# room8266.net
KiCad netlist of a schematic drawn in EAGLE
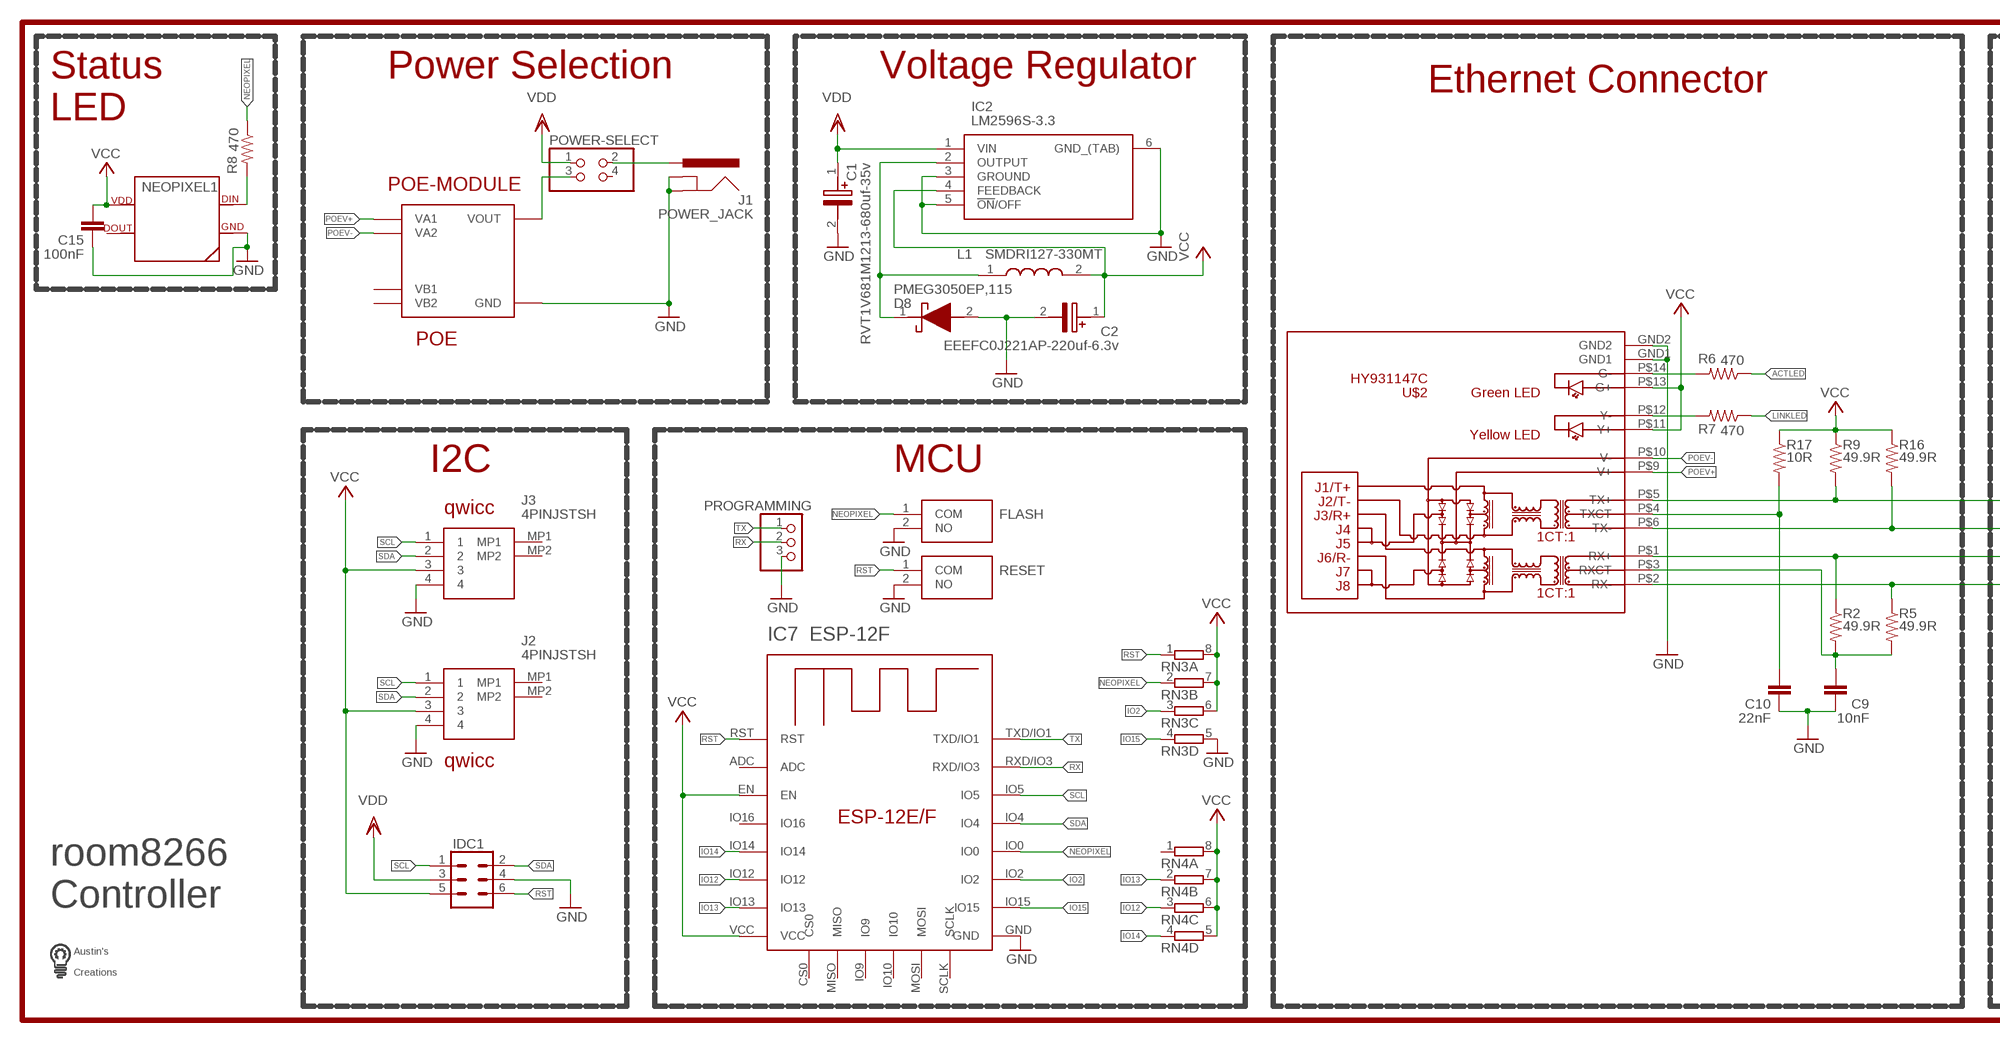
[diagram p0: schematic, sheet 1, part 1 of 2]
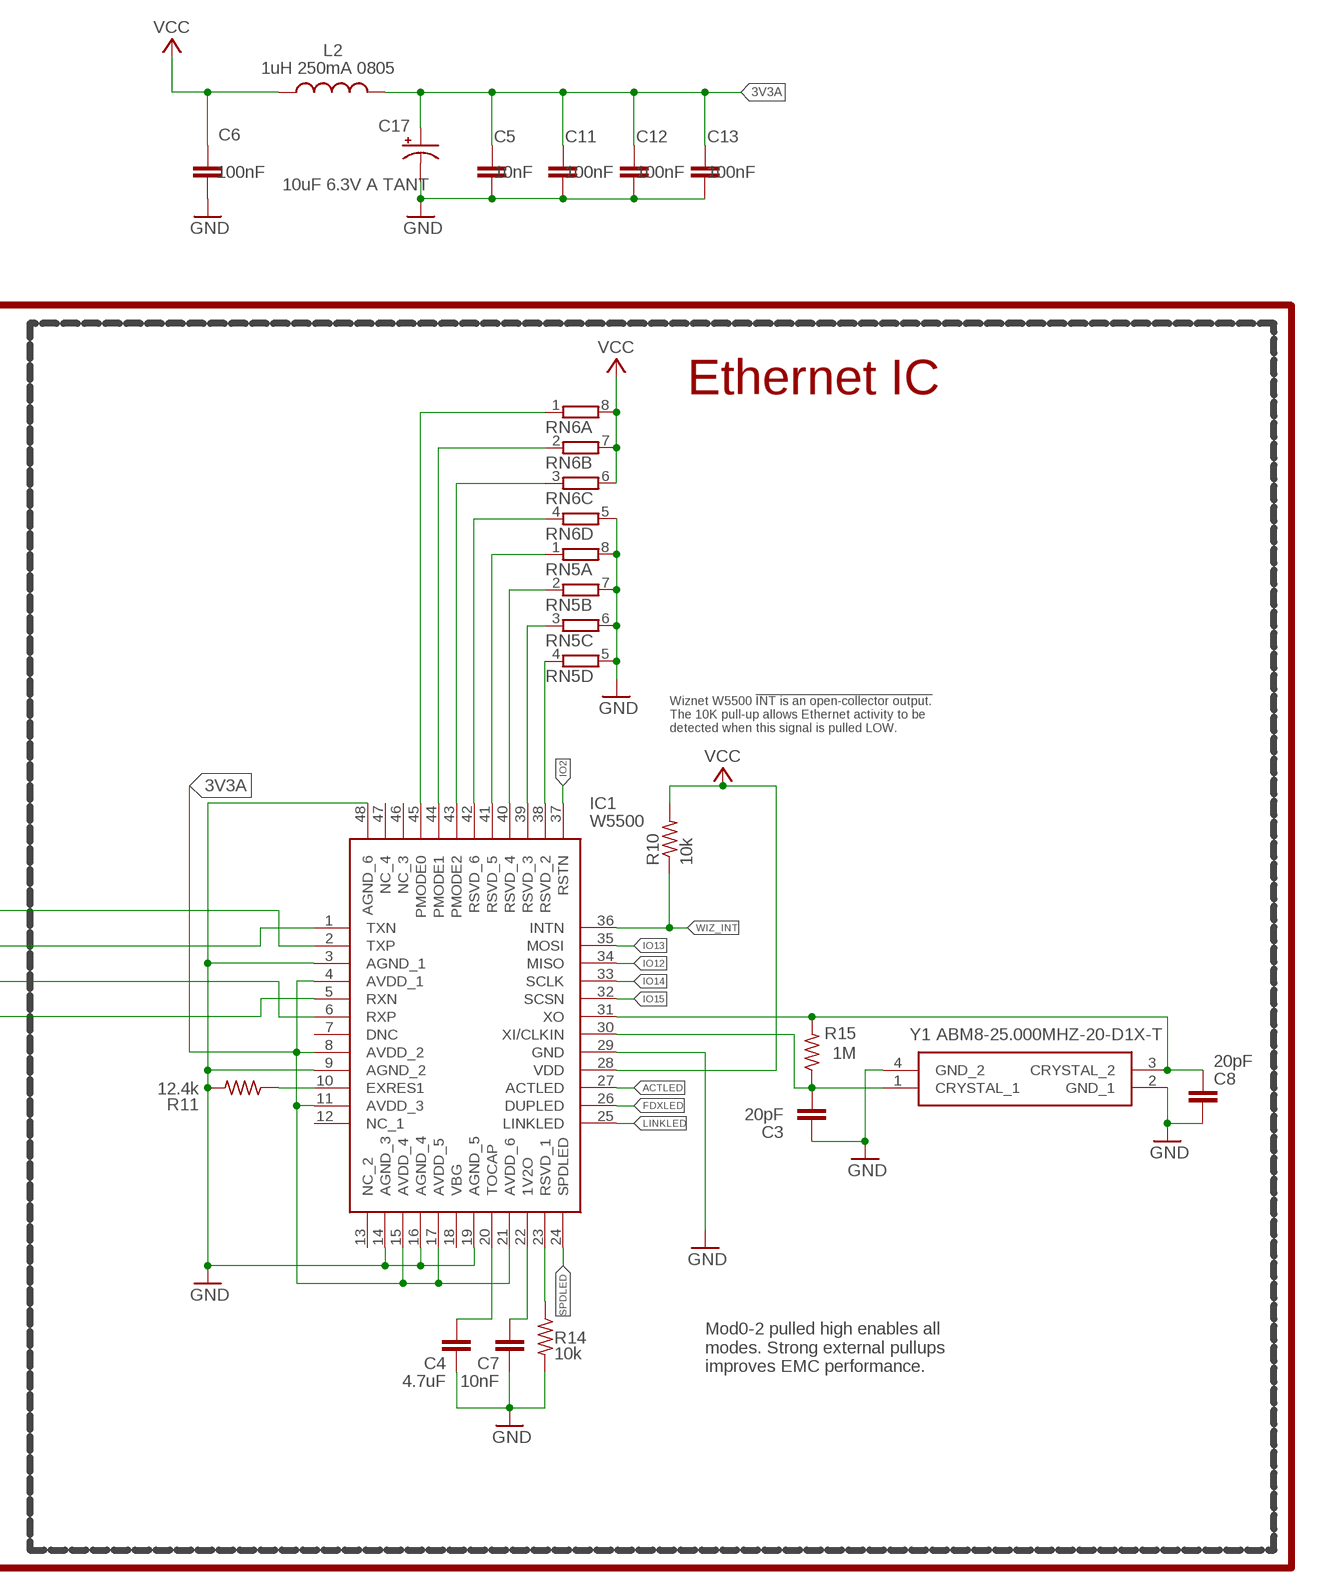
[diagram p1: schematic, sheet 1, part 2 of 2]

(export (version "E")
  (design (tool "Eeschema 10.0.6"))
  (components
    (comp (ref "C1")
      (value "RVT1V681M1213-680uf-35v")
      (footprint "eagle-import:CAPAE1350X1400N")
      (fields
        (field (name "MANUFACTURER_PART_NUMBER") "EEE-HD1V681AQ")
        (field (name "MOUSER_PART_NUMBER") "667-EEE-HD1V681AQ")
      )
      (libsource (lib "eagle-import") (part "EEE-HD1V681AQ"))
    )
    (comp (ref "C2")
      (value "EEEFC0J221AP-220uf-6.3v")
      (footprint "eagle-import:CAPAE830X650N")
      (fields (field (name "MANUFACTURER_PART_NUMBER") "EEEFC0J221AP"))
      (libsource (lib "eagle-import") (part "EEEFC0J221AP"))
    )
    (comp (ref "C3")
      (value "20pF")
      (footprint "eagle-import:C0603")
      (libsource (lib "eagle-import") (part "resistor_348_C-EUC0603"))
    )
    (comp (ref "C4")
      (value "4.7uF")
      (footprint "eagle-import:C0603")
      (libsource (lib "eagle-import") (part "resistor_348_C-EUC0603"))
    )
    (comp (ref "C5")
      (value "10nF")
      (footprint "eagle-import:C0603")
      (libsource (lib "eagle-import") (part "C-EUC0603"))
    )
    (comp (ref "C6")
      (value "100nF")
      (footprint "eagle-import:C0603")
      (libsource (lib "eagle-import") (part "C-EUC0603"))
    )
    (comp (ref "C7")
      (value "10nF")
      (footprint "eagle-import:C0603")
      (libsource (lib "eagle-import") (part "resistor_348_C-EUC0603"))
    )
    (comp (ref "C8")
      (value "20pF")
      (footprint "eagle-import:C0603")
      (libsource (lib "eagle-import") (part "resistor_348_C-EUC0603"))
    )
    (comp (ref "C9")
      (value "10nF")
      (footprint "eagle-import:C0603")
      (libsource (lib "eagle-import") (part "resistor_348_C-EUC0603"))
    )
    (comp (ref "C10")
      (value "22nF")
      (footprint "eagle-import:C0603")
      (libsource (lib "eagle-import") (part "resistor_348_C-EUC0603"))
    )
    (comp (ref "C11")
      (value "100nF")
      (footprint "eagle-import:C0603")
      (libsource (lib "eagle-import") (part "C-EUC0603"))
    )
    (comp (ref "C12")
      (value "100nF")
      (footprint "eagle-import:C0603")
      (libsource (lib "eagle-import") (part "C-EUC0603"))
    )
    (comp (ref "C13")
      (value "100nF")
      (footprint "eagle-import:C0603")
      (libsource (lib "eagle-import") (part "C-EUC0603"))
    )
    (comp (ref "C15")
      (value "100nF")
      (footprint "eagle-import:C0603")
      (libsource (lib "eagle-import") (part "resistor_348_C-EUC0603"))
    )
    (comp (ref "C17")
      (value "10uF 6.3V A TANT")
      (footprint "eagle-import:A_3216-18W")
      (libsource (lib "eagle-import") (part "CPOL-USA/3216-18W"))
    )
    (comp (ref "D8")
      (value "PMEG3050EP,115")
      (footprint "eagle-import:PMEG3050EP115")
      (fields (field (name "MOUSER_PART_NUMBER") "771-PMEG3050EP115"))
      (libsource (lib "eagle-import") (part "PMEG3050EP,115"))
    )
    (comp (ref "FLASH")
      (value "PTS636_SM25F_SMTR_LFS")
      (footprint "eagle-import:PTS636SM25FSMTRLFS")
      (fields
        (field (name "ARROW_PART_NUMBER") "PTS636 SM25F SMTR LFS")
        (field (name "MOUSER_PART_NUMBER") "611-PTS636SM25FSMTRL")
      )
      (libsource (lib "eagle-import") (part "PTS636_SM25F_SMTR_LFS"))
    )
    (comp (ref "IC1")
      (value "W5500")
      (footprint "eagle-import:QFP50P900X900X160-48N")
      (fields (field (name "MOUSER_PART_NUMBER") "950-W5500"))
      (libsource (lib "eagle-import") (part "W5500"))
    )
    (comp (ref "IC2")
      (value "LM2596S-3.3")
      (footprint "eagle-import:TO170P1435X465-6N")
      (fields
        (field (name "MANUFACTURER_PART_NUMBER") "LM2596S-3.3/NOPB")
        (field (name "MOUSER_PART_NUMBER") "926-LM2596S-3.3/NOPB")
      )
      (libsource (lib "eagle-import") (part "LM2596S-3.3_NOPB"))
    )
    (comp (ref "IC7")
      (value "ESP-12F")
      (footprint "eagle-import:ESP-12E")
      (libsource (lib "eagle-import") (part "ESP-12E/F"))
    )
    (comp (ref "IDC1")
      (value "CONN_03X2SHROUD")
      (footprint "eagle-import:2X3-SHROUDED")
      (libsource (lib "eagle-import") (part "CONN_03X2SHROUD"))
    )
    (comp (ref "J1")
      (value "POWER_JACK")
      (footprint "eagle-import:POWER_JACK_PTH")
      (libsource (lib "eagle-import") (part "POWER_JACK"))
    )
    (comp (ref "J2")
      (value "4PINJSTSH")
      (footprint "eagle-import:665104131822")
      (fields
        (field (name "MANUFACTURER_PART_NUMBER") "665104131822")
        (field (name "MOUSER_PART_NUMBER") "710-665104131822")
      )
      (libsource (lib "eagle-import") (part "4PINJSTSH"))
    )
    (comp (ref "J3")
      (value "4PINJSTSH")
      (footprint "eagle-import:665104131822")
      (fields
        (field (name "MANUFACTURER_PART_NUMBER") "665104131822")
        (field (name "MOUSER_PART_NUMBER") "710-665104131822")
      )
      (libsource (lib "eagle-import") (part "4PINJSTSH"))
    )
    (comp (ref "L1")
      (value "SMDRI127-330MT")
      (footprint "eagle-import:INDPM120120X800N")
      (fields
        (field (name "MANUFACTURER_PART_NUMBER") "CDRH127/LDNP-330MC")
        (field (name "MOUSER_PART_NUMBER") "851-CDRH127LDNP330MC")
      )
      (libsource (lib "eagle-import") (part "CDRH127_LDNP-330MC"))
    )
    (comp (ref "L2")
      (value "1uH 250mA 0805")
      (footprint "eagle-import:L2012C")
      (libsource (lib "eagle-import") (part "L-USL2012C"))
    )
    (comp (ref "NEOPIXEL1")
      (value "SK6812NEOPIXEL5050")
      (footprint "eagle-import:SK6812")
      (libsource (lib "eagle-import") (part "SK68125050NEOPIXEL"))
    )
    (comp (ref "POE-MODULE")
      (value "POE")
      (footprint "eagle-import:DP1435")
      (libsource (lib "eagle-import") (part "POE"))
    )
    (comp (ref "POWER-SELECT")
      (value "PINHD-2X2")
      (footprint "eagle-import:2X02")
      (libsource (lib "eagle-import") (part "PINHD-2X2"))
    )
    (comp (ref "PROGRAMMING")
      (value "PINHD-1X3")
      (footprint "eagle-import:1X03")
      (libsource (lib "eagle-import") (part "PINHD-1X3"))
    )
    (comp (ref "R2")
      (value "49.9R")
      (footprint "eagle-import:R0603")
      (libsource (lib "eagle-import") (part "R-US_R0603"))
    )
    (comp (ref "R5")
      (value "49.9R")
      (footprint "eagle-import:R0603")
      (libsource (lib "eagle-import") (part "R-US_R0603"))
    )
    (comp (ref "R6")
      (value "470")
      (footprint "eagle-import:R0603")
      (libsource (lib "eagle-import") (part "R-US_R0603"))
    )
    (comp (ref "R7")
      (value "470")
      (footprint "eagle-import:R0603")
      (libsource (lib "eagle-import") (part "R-US_R0603"))
    )
    (comp (ref "R8")
      (value "470")
      (footprint "eagle-import:R0603")
      (libsource (lib "eagle-import") (part "R-US_R0603"))
    )
    (comp (ref "R9")
      (value "49.9R")
      (footprint "eagle-import:R0603")
      (libsource (lib "eagle-import") (part "R-US_R0603"))
    )
    (comp (ref "R10")
      (value "10k")
      (footprint "eagle-import:R0603")
      (libsource (lib "eagle-import") (part "R-US_R0603"))
    )
    (comp (ref "R11")
      (value "12.4k")
      (footprint "eagle-import:R0603")
      (libsource (lib "eagle-import") (part "R-US_R0603"))
    )
    (comp (ref "R14")
      (value "10k")
      (footprint "eagle-import:R0603")
      (libsource (lib "eagle-import") (part "R-US_R0603"))
    )
    (comp (ref "R15")
      (value "1M")
      (footprint "eagle-import:R0603")
      (libsource (lib "eagle-import") (part "R-US_R0603"))
    )
    (comp (ref "R16")
      (value "49.9R")
      (footprint "eagle-import:R0603")
      (libsource (lib "eagle-import") (part "R-US_R0603"))
    )
    (comp (ref "R17")
      (value "10R")
      (footprint "eagle-import:R0603")
      (libsource (lib "eagle-import") (part "R-US_R0603"))
    )
    (comp (ref "RESET")
      (value "PTS636_SM25F_SMTR_LFS")
      (footprint "eagle-import:PTS636SM25FSMTRLFS")
      (fields
        (field (name "ARROW_PART_NUMBER") "PTS636 SM25F SMTR LFS")
        (field (name "MOUSER_PART_NUMBER") "611-PTS636SM25FSMTRL")
      )
      (libsource (lib "eagle-import") (part "PTS636_SM25F_SMTR_LFS"))
    )
    (comp (ref "RN3")
      (value "4R-N0603-ARC")
      (footprint "eagle-import:0603-ARC")
      (libsource (lib "eagle-import") (part "4R-N0603-ARC"))
    )
    (comp (ref "RN4")
      (value "4R-N0603-ARC")
      (footprint "eagle-import:0603-ARC")
      (libsource (lib "eagle-import") (part "4R-N0603-ARC"))
    )
    (comp (ref "RN5")
      (value "4R-N0603-ARC")
      (footprint "eagle-import:0603-ARC")
      (libsource (lib "eagle-import") (part "4R-N0603-ARC"))
    )
    (comp (ref "RN6")
      (value "4R-N0603-ARC")
      (footprint "eagle-import:0603-ARC")
      (libsource (lib "eagle-import") (part "4R-N0603-ARC"))
    )
    (comp (ref "U$1")
      (value "LOGOMED")
      (footprint "eagle-import:LOGOMED")
      (libsource (lib "eagle-import") (part "LOGOMED"))
    )
    (comp (ref "U$2")
      (value "HY931147C")
      (footprint "eagle-import:HY931147C")
      (libsource (lib "eagle-import") (part "HY931147C"))
    )
    (comp (ref "Y1")
      (value "ABM8-25.000MHZ-20-D1X-T")
      (footprint "eagle-import:ABM825000MHZ10B1UT")
      (fields
        (field (name "MANUFACTURER_PART_NUMBER") "ABM8-25.000MHz-20-D1X-T")
        (field (name "MOUSER_PART_NUMBER") "815-M825000MHZ20D1XT")
      )
      (libsource (lib "eagle-import") (part "ABM8-25.000MHZ-20-D1X-T"))
    )
  )
  (nets
    (net (code "1") (name "3V3A") (class "Default")
      (node (ref "C11") (pin "1") (pinfunction "1_1") (pintype "passive"))
      (node (ref "C12") (pin "1") (pinfunction "1_1") (pintype "passive"))
      (node (ref "C13") (pin "1") (pinfunction "1_1") (pintype "passive"))
      (node (ref "C17") (pin "+") (pinfunction "+_+") (pintype "passive"))
      (node (ref "C5") (pin "1") (pinfunction "1_1") (pintype "passive"))
      (node (ref "IC1") (pin "11") (pinfunction "AVDD_3_11") (pintype "bidirectional"))
      (node (ref "IC1") (pin "15") (pinfunction "AVDD_4_15") (pintype "bidirectional"))
      (node (ref "IC1") (pin "17") (pinfunction "AVDD_5_17") (pintype "bidirectional"))
      (node (ref "IC1") (pin "21") (pinfunction "AVDD_6_21") (pintype "bidirectional"))
      (node (ref "IC1") (pin "4") (pinfunction "AVDD_1_4") (pintype "bidirectional"))
      (node (ref "IC1") (pin "8") (pinfunction "AVDD_2_8") (pintype "bidirectional"))
      (node (ref "L2") (pin "2") (pinfunction "2_2") (pintype "passive"))
    )
    (net (code "2") (name "ACTLED") (class "Default")
      (node (ref "IC1") (pin "27") (pinfunction "ACTLED_27") (pintype "bidirectional"))
      (node (ref "R6") (pin "1") (pinfunction "1_1") (pintype "passive"))
    )
    (net (code "3") (name "FDXLED") (class "Default")
      (node (ref "IC1") (pin "26") (pinfunction "DUPLED_26") (pintype "bidirectional"))
    )
    (net (code "4") (name "GND") (class "Default")
      (node (ref "C1") (pin "2") (pinfunction "-_2") (pintype "bidirectional"))
      (node (ref "C10") (pin "1") (pinfunction "1_1") (pintype "passive"))
      (node (ref "C11") (pin "2") (pinfunction "2_2") (pintype "passive"))
      (node (ref "C12") (pin "2") (pinfunction "2_2") (pintype "passive"))
      (node (ref "C13") (pin "2") (pinfunction "2_2") (pintype "passive"))
      (node (ref "C15") (pin "1") (pinfunction "1_1") (pintype "passive"))
      (node (ref "C17") (pin "-") (pinfunction "-_-") (pintype "passive"))
      (node (ref "C2") (pin "2") (pinfunction "-_2") (pintype "bidirectional"))
      (node (ref "C3") (pin "1") (pinfunction "1_1") (pintype "passive"))
      (node (ref "C4") (pin "1") (pinfunction "1_1") (pintype "passive"))
      (node (ref "C5") (pin "2") (pinfunction "2_2") (pintype "passive"))
      (node (ref "C6") (pin "2") (pinfunction "2_2") (pintype "passive"))
      (node (ref "C7") (pin "1") (pinfunction "1_1") (pintype "passive"))
      (node (ref "C8") (pin "1") (pinfunction "1_1") (pintype "passive"))
      (node (ref "C9") (pin "1") (pinfunction "1_1") (pintype "passive"))
      (node (ref "D8") (pin "2") (pinfunction "A_2") (pintype "bidirectional"))
      (node (ref "FLASH") (pin "2") (pinfunction "NO_2") (pintype "bidirectional"))
      (node (ref "IC1") (pin "14") (pinfunction "AGND_3_14") (pintype "bidirectional"))
      (node (ref "IC1") (pin "16") (pinfunction "AGND_4_16") (pintype "bidirectional"))
      (node (ref "IC1") (pin "19") (pinfunction "AGND_5_19") (pintype "bidirectional"))
      (node (ref "IC1") (pin "29") (pinfunction "GND_29") (pintype "bidirectional"))
      (node (ref "IC1") (pin "3") (pinfunction "AGND_1_3") (pintype "bidirectional"))
      (node (ref "IC1") (pin "48") (pinfunction "AGND_6_48") (pintype "bidirectional"))
      (node (ref "IC1") (pin "9") (pinfunction "AGND_2_9") (pintype "bidirectional"))
      (node (ref "IC2") (pin "3") (pinfunction "GROUND_3") (pintype "bidirectional"))
      (node (ref "IC2") (pin "5") (pinfunction "~{ON}/OFF_5") (pintype "bidirectional"))
      (node (ref "IC2") (pin "6") (pinfunction "GND_(TAB)_6") (pintype "power_in"))
      (node (ref "IC7") (pin "GND") (pinfunction "GND_GND") (pintype "power_in"))
      (node (ref "IDC1") (pin "4") (pinfunction "4_4") (pintype "bidirectional"))
      (node (ref "J1") (pin "GND") (pinfunction "GND_GND") (pintype "bidirectional"))
      (node (ref "J1") (pin "GNDBREAK") (pinfunction "GNDBREAK_GNDBREAK") (pintype "bidirectional"))
      (node (ref "J2") (pin "4") (pinfunction "4_4") (pintype "bidirectional"))
      (node (ref "J3") (pin "4") (pinfunction "4_4") (pintype "bidirectional"))
      (node (ref "NEOPIXEL1") (pin "3") (pinfunction "GND_3") (pintype "bidirectional"))
      (node (ref "POE-MODULE") (pin "GND") (pinfunction "GND_GND") (pintype "bidirectional"))
      (node (ref "PROGRAMMING") (pin "3") (pinfunction "3_3") (pintype "passive"))
      (node (ref "R11") (pin "2") (pinfunction "2_2") (pintype "passive"))
      (node (ref "R14") (pin "2") (pinfunction "2_2") (pintype "passive"))
      (node (ref "RESET") (pin "2") (pinfunction "NO_2") (pintype "bidirectional"))
      (node (ref "RN3") (pin "5") (pinfunction "2_5") (pintype "passive"))
      (node (ref "RN5") (pin "5") (pinfunction "2_5") (pintype "passive"))
      (node (ref "RN5") (pin "6") (pinfunction "2_6") (pintype "passive"))
      (node (ref "RN5") (pin "7") (pinfunction "2_7") (pintype "passive"))
      (node (ref "RN5") (pin "8") (pinfunction "2_8") (pintype "passive"))
      (node (ref "RN6") (pin "5") (pinfunction "2_5") (pintype "passive"))
      (node (ref "U$2") (pin "GND1") (pinfunction "GND1_GND1") (pintype "bidirectional"))
      (node (ref "U$2") (pin "GND2") (pinfunction "GND2_GND2") (pintype "bidirectional"))
      (node (ref "Y1") (pin "2") (pinfunction "GND_1_2") (pintype "bidirectional"))
      (node (ref "Y1") (pin "4") (pinfunction "GND_2_4") (pintype "bidirectional"))
    )
    (net (code "5") (name "IO2") (class "Default")
      (node (ref "IC1") (pin "37") (pinfunction "RSTN_37") (pintype "bidirectional"))
      (node (ref "IC7") (pin "IO2") (pinfunction "IO2_IO2") (pintype "bidirectional"))
      (node (ref "RN3") (pin "3") (pinfunction "1_3") (pintype "passive"))
    )
    (net (code "6") (name "IO12") (class "Default")
      (node (ref "IC1") (pin "34") (pinfunction "MISO_34") (pintype "bidirectional"))
      (node (ref "IC7") (pin "IO12") (pinfunction "IO12_IO12") (pintype "bidirectional"))
      (node (ref "RN4") (pin "3") (pinfunction "1_3") (pintype "passive"))
    )
    (net (code "7") (name "IO13") (class "Default")
      (node (ref "IC1") (pin "35") (pinfunction "MOSI_35") (pintype "bidirectional"))
      (node (ref "IC7") (pin "IO13") (pinfunction "IO13_IO13") (pintype "bidirectional"))
      (node (ref "RN4") (pin "2") (pinfunction "1_2") (pintype "passive"))
    )
    (net (code "8") (name "IO14") (class "Default")
      (node (ref "IC1") (pin "33") (pinfunction "SCLK_33") (pintype "bidirectional"))
      (node (ref "IC7") (pin "IO14") (pinfunction "IO14_IO14") (pintype "bidirectional"))
      (node (ref "RN4") (pin "4") (pinfunction "1_4") (pintype "passive"))
    )
    (net (code "9") (name "IO15") (class "Default")
      (node (ref "IC1") (pin "32") (pinfunction "SCSN_32") (pintype "bidirectional"))
      (node (ref "IC7") (pin "IO15") (pinfunction "IO15_IO15") (pintype "bidirectional"))
      (node (ref "RN3") (pin "4") (pinfunction "1_4") (pintype "passive"))
    )
    (net (code "10") (name "LINKLED") (class "Default")
      (node (ref "IC1") (pin "25") (pinfunction "LINKLED_25") (pintype "bidirectional"))
      (node (ref "R7") (pin "1") (pinfunction "1_1") (pintype "passive"))
    )
    (net (code "11") (name "NEOPIXEL") (class "Default")
      (node (ref "FLASH") (pin "1") (pinfunction "COM_1") (pintype "bidirectional"))
      (node (ref "IC7") (pin "IO0") (pinfunction "IO0_IO0") (pintype "bidirectional"))
      (node (ref "R8") (pin "1") (pinfunction "1_1") (pintype "passive"))
      (node (ref "RN3") (pin "2") (pinfunction "1_2") (pintype "passive"))
    )
    (net (code "12") (name "Net-(D8-K)") (class "Default")
      (node (ref "D8") (pin "1") (pinfunction "K_1") (pintype "bidirectional"))
      (node (ref "IC2") (pin "2") (pinfunction "OUTPUT_2") (pintype "output"))
      (node (ref "L1") (pin "1") (pinfunction "1_1") (pintype "bidirectional"))
    )
    (net (code "13") (name "Net-(IC1-1V2O)") (class "Default")
      (node (ref "C7") (pin "2") (pinfunction "2_2") (pintype "passive"))
      (node (ref "IC1") (pin "22") (pinfunction "1V2O_22") (pintype "bidirectional"))
    )
    (net (code "14") (name "Net-(IC1-EXRES1)") (class "Default")
      (node (ref "IC1") (pin "10") (pinfunction "EXRES1_10") (pintype "bidirectional"))
      (node (ref "R11") (pin "1") (pinfunction "1_1") (pintype "passive"))
    )
    (net (code "15") (name "Net-(IC1-PMODE0)") (class "Default")
      (node (ref "IC1") (pin "45") (pinfunction "PMODE0_45") (pintype "bidirectional"))
      (node (ref "RN6") (pin "1") (pinfunction "1_1") (pintype "passive"))
    )
    (net (code "16") (name "Net-(IC1-PMODE1)") (class "Default")
      (node (ref "IC1") (pin "44") (pinfunction "PMODE1_44") (pintype "bidirectional"))
      (node (ref "RN6") (pin "2") (pinfunction "1_2") (pintype "passive"))
    )
    (net (code "17") (name "Net-(IC1-PMODE2)") (class "Default")
      (node (ref "IC1") (pin "43") (pinfunction "PMODE2_43") (pintype "bidirectional"))
      (node (ref "RN6") (pin "3") (pinfunction "1_3") (pintype "passive"))
    )
    (net (code "18") (name "Net-(IC1-RSVD_1)") (class "Default")
      (node (ref "IC1") (pin "23") (pinfunction "RSVD_1_23") (pintype "bidirectional"))
      (node (ref "R14") (pin "1") (pinfunction "1_1") (pintype "passive"))
    )
    (net (code "19") (name "Net-(IC1-RSVD_2)") (class "Default")
      (node (ref "IC1") (pin "38") (pinfunction "RSVD_2_38") (pintype "bidirectional"))
      (node (ref "RN5") (pin "4") (pinfunction "1_4") (pintype "passive"))
    )
    (net (code "20") (name "Net-(IC1-RSVD_3)") (class "Default")
      (node (ref "IC1") (pin "39") (pinfunction "RSVD_3_39") (pintype "bidirectional"))
      (node (ref "RN5") (pin "3") (pinfunction "1_3") (pintype "passive"))
    )
    (net (code "21") (name "Net-(IC1-RSVD_4)") (class "Default")
      (node (ref "IC1") (pin "40") (pinfunction "RSVD_4_40") (pintype "bidirectional"))
      (node (ref "RN5") (pin "2") (pinfunction "1_2") (pintype "passive"))
    )
    (net (code "22") (name "Net-(IC1-RSVD_5)") (class "Default")
      (node (ref "IC1") (pin "41") (pinfunction "RSVD_5_41") (pintype "bidirectional"))
      (node (ref "RN5") (pin "1") (pinfunction "1_1") (pintype "passive"))
    )
    (net (code "23") (name "Net-(IC1-RSVD_6)") (class "Default")
      (node (ref "IC1") (pin "42") (pinfunction "RSVD_6_42") (pintype "bidirectional"))
      (node (ref "RN6") (pin "4") (pinfunction "1_4") (pintype "passive"))
    )
    (net (code "24") (name "Net-(IC1-RXN)") (class "Default")
      (node (ref "IC1") (pin "5") (pinfunction "RXN_5") (pintype "bidirectional"))
      (node (ref "R5") (pin "1") (pinfunction "1_1") (pintype "passive"))
      (node (ref "U$2") (pin "P$2") (pinfunction "RX-_P$2") (pintype "bidirectional"))
    )
    (net (code "25") (name "Net-(IC1-RXP)") (class "Default")
      (node (ref "IC1") (pin "6") (pinfunction "RXP_6") (pintype "bidirectional"))
      (node (ref "R2") (pin "1") (pinfunction "1_1") (pintype "passive"))
      (node (ref "U$2") (pin "P$1") (pinfunction "RX+_P$1") (pintype "bidirectional"))
    )
    (net (code "26") (name "Net-(IC1-TOCAP)") (class "Default")
      (node (ref "C4") (pin "2") (pinfunction "2_2") (pintype "passive"))
      (node (ref "IC1") (pin "20") (pinfunction "TOCAP_20") (pintype "bidirectional"))
    )
    (net (code "27") (name "Net-(IC1-TXN)") (class "Default")
      (node (ref "IC1") (pin "1") (pinfunction "TXN_1") (pintype "bidirectional"))
      (node (ref "R16") (pin "2") (pinfunction "2_2") (pintype "passive"))
      (node (ref "U$2") (pin "P$6") (pinfunction "TX-_P$6") (pintype "bidirectional"))
    )
    (net (code "28") (name "Net-(IC1-TXP)") (class "Default")
      (node (ref "IC1") (pin "2") (pinfunction "TXP_2") (pintype "bidirectional"))
      (node (ref "R9") (pin "2") (pinfunction "2_2") (pintype "passive"))
      (node (ref "U$2") (pin "P$5") (pinfunction "TX+_P$5") (pintype "bidirectional"))
    )
    (net (code "29") (name "Net-(IC1-XI{slash}CLKIN)") (class "Default")
      (node (ref "C3") (pin "2") (pinfunction "2_2") (pintype "passive"))
      (node (ref "IC1") (pin "30") (pinfunction "XI/CLKIN_30") (pintype "bidirectional"))
      (node (ref "R15") (pin "1") (pinfunction "1_1") (pintype "passive"))
      (node (ref "Y1") (pin "1") (pinfunction "CRYSTAL_1_1") (pintype "bidirectional"))
    )
    (net (code "30") (name "Net-(IC1-XO)") (class "Default")
      (node (ref "C8") (pin "2") (pinfunction "2_2") (pintype "passive"))
      (node (ref "IC1") (pin "31") (pinfunction "XO_31") (pintype "bidirectional"))
      (node (ref "R15") (pin "2") (pinfunction "2_2") (pintype "passive"))
      (node (ref "Y1") (pin "3") (pinfunction "CRYSTAL_2_3") (pintype "bidirectional"))
    )
    (net (code "31") (name "Net-(J1-PadPWR)") (class "Default")
      (node (ref "J1") (pin "PWR") (pinfunction "PWR_PWR") (pintype "bidirectional"))
      (node (ref "POWER-SELECT") (pin "2") (pinfunction "2_2") (pintype "passive"))
    )
    (net (code "32") (name "Net-(NEOPIXEL1-DIN)") (class "Default")
      (node (ref "NEOPIXEL1") (pin "4") (pinfunction "DIN_4") (pintype "bidirectional"))
      (node (ref "R8") (pin "2") (pinfunction "2_2") (pintype "passive"))
    )
    (net (code "33") (name "Net-(POE-MODULE-PadVOUT)") (class "Default")
      (node (ref "POE-MODULE") (pin "VOUT") (pinfunction "VOUT_VOUT") (pintype "bidirectional"))
      (node (ref "POWER-SELECT") (pin "3") (pinfunction "3_3") (pintype "passive"))
    )
    (net (code "34") (name "Net-(U$2-G-)") (class "Default")
      (node (ref "R6") (pin "2") (pinfunction "2_2") (pintype "passive"))
      (node (ref "U$2") (pin "P$14") (pinfunction "G-_P$14") (pintype "bidirectional"))
    )
    (net (code "35") (name "Net-(U$2-RXCT)") (class "Default")
      (node (ref "C9") (pin "2") (pinfunction "2_2") (pintype "passive"))
      (node (ref "R2") (pin "2") (pinfunction "2_2") (pintype "passive"))
      (node (ref "R5") (pin "2") (pinfunction "2_2") (pintype "passive"))
      (node (ref "U$2") (pin "P$3") (pinfunction "RXCT_P$3") (pintype "bidirectional"))
    )
    (net (code "36") (name "Net-(U$2-TXCT)") (class "Default")
      (node (ref "C10") (pin "2") (pinfunction "2_2") (pintype "passive"))
      (node (ref "R17") (pin "2") (pinfunction "2_2") (pintype "passive"))
      (node (ref "U$2") (pin "P$4") (pinfunction "TXCT_P$4") (pintype "bidirectional"))
    )
    (net (code "37") (name "Net-(U$2-Y-)") (class "Default")
      (node (ref "R7") (pin "2") (pinfunction "2_2") (pintype "passive"))
      (node (ref "U$2") (pin "P$12") (pinfunction "Y-_P$12") (pintype "bidirectional"))
    )
    (net (code "38") (name "POEV+") (class "Default")
      (node (ref "POE-MODULE") (pin "VA1") (pinfunction "VA1_VA1") (pintype "bidirectional"))
      (node (ref "U$2") (pin "P$9") (pinfunction "V+_P$9") (pintype "bidirectional"))
    )
    (net (code "39") (name "POEV-") (class "Default")
      (node (ref "POE-MODULE") (pin "VA2") (pinfunction "VA2_VA2") (pintype "bidirectional"))
      (node (ref "U$2") (pin "P$10") (pinfunction "V-_P$10") (pintype "bidirectional"))
    )
    (net (code "40") (name "RST") (class "Default")
      (node (ref "IC7") (pin "RST") (pinfunction "RST_RST") (pintype "input"))
      (node (ref "IDC1") (pin "6") (pinfunction "6_6") (pintype "bidirectional"))
      (node (ref "RESET") (pin "1") (pinfunction "COM_1") (pintype "bidirectional"))
      (node (ref "RN3") (pin "1") (pinfunction "1_1") (pintype "passive"))
    )
    (net (code "41") (name "RX") (class "Default")
      (node (ref "IC7") (pin "RXD/IO3") (pinfunction "RXD/IO3_RXD/IO3") (pintype "bidirectional"))
      (node (ref "PROGRAMMING") (pin "2") (pinfunction "2_2") (pintype "passive"))
    )
    (net (code "42") (name "SCL") (class "Default")
      (node (ref "IC7") (pin "IO5") (pinfunction "IO5_IO5") (pintype "bidirectional"))
      (node (ref "IDC1") (pin "1") (pinfunction "1_1") (pintype "bidirectional"))
      (node (ref "J2") (pin "1") (pinfunction "1_1") (pintype "bidirectional"))
      (node (ref "J3") (pin "1") (pinfunction "1_1") (pintype "bidirectional"))
    )
    (net (code "43") (name "SDA") (class "Default")
      (node (ref "IC7") (pin "IO4") (pinfunction "IO4_IO4") (pintype "bidirectional"))
      (node (ref "IDC1") (pin "2") (pinfunction "2_2") (pintype "bidirectional"))
      (node (ref "J2") (pin "2") (pinfunction "2_2") (pintype "bidirectional"))
      (node (ref "J3") (pin "2") (pinfunction "2_2") (pintype "bidirectional"))
    )
    (net (code "44") (name "SPDLED") (class "Default")
      (node (ref "IC1") (pin "24") (pinfunction "SPDLED_24") (pintype "bidirectional"))
    )
    (net (code "45") (name "TX") (class "Default")
      (node (ref "IC7") (pin "TXD/IO1") (pinfunction "TXD/IO1_TXD/IO1") (pintype "bidirectional"))
      (node (ref "PROGRAMMING") (pin "1") (pinfunction "1_1") (pintype "passive"))
    )
    (net (code "46") (name "VCC") (class "Default")
      (node (ref "C15") (pin "2") (pinfunction "2_2") (pintype "passive"))
      (node (ref "C2") (pin "1") (pinfunction "+_1") (pintype "bidirectional"))
      (node (ref "C6") (pin "1") (pinfunction "1_1") (pintype "passive"))
      (node (ref "IC1") (pin "28") (pinfunction "VDD_28") (pintype "bidirectional"))
      (node (ref "IC2") (pin "4") (pinfunction "FEEDBACK_4") (pintype "bidirectional"))
      (node (ref "IC7") (pin "EN") (pinfunction "EN_EN") (pintype "bidirectional"))
      (node (ref "IC7") (pin "VCC") (pinfunction "VCC_VCC") (pintype "power_in"))
      (node (ref "IDC1") (pin "5") (pinfunction "5_5") (pintype "bidirectional"))
      (node (ref "J2") (pin "3") (pinfunction "3_3") (pintype "bidirectional"))
      (node (ref "J3") (pin "3") (pinfunction "3_3") (pintype "bidirectional"))
      (node (ref "L1") (pin "2") (pinfunction "2_2") (pintype "bidirectional"))
      (node (ref "L2") (pin "1") (pinfunction "1_1") (pintype "passive"))
      (node (ref "NEOPIXEL1") (pin "1") (pinfunction "VDD_1") (pintype "bidirectional"))
      (node (ref "R10") (pin "2") (pinfunction "2_2") (pintype "passive"))
      (node (ref "R16") (pin "1") (pinfunction "1_1") (pintype "passive"))
      (node (ref "R17") (pin "1") (pinfunction "1_1") (pintype "passive"))
      (node (ref "R9") (pin "1") (pinfunction "1_1") (pintype "passive"))
      (node (ref "RN3") (pin "6") (pinfunction "2_6") (pintype "passive"))
      (node (ref "RN3") (pin "7") (pinfunction "2_7") (pintype "passive"))
      (node (ref "RN3") (pin "8") (pinfunction "2_8") (pintype "passive"))
      (node (ref "RN4") (pin "5") (pinfunction "2_5") (pintype "passive"))
      (node (ref "RN4") (pin "6") (pinfunction "2_6") (pintype "passive"))
      (node (ref "RN4") (pin "7") (pinfunction "2_7") (pintype "passive"))
      (node (ref "RN4") (pin "8") (pinfunction "2_8") (pintype "passive"))
      (node (ref "RN6") (pin "6") (pinfunction "2_6") (pintype "passive"))
      (node (ref "RN6") (pin "7") (pinfunction "2_7") (pintype "passive"))
      (node (ref "RN6") (pin "8") (pinfunction "2_8") (pintype "passive"))
      (node (ref "U$2") (pin "P$11") (pinfunction "Y+_P$11") (pintype "bidirectional"))
      (node (ref "U$2") (pin "P$13") (pinfunction "G+_P$13") (pintype "bidirectional"))
    )
    (net (code "47") (name "VDD") (class "Default")
      (node (ref "C1") (pin "1") (pinfunction "+_1") (pintype "bidirectional"))
      (node (ref "IC2") (pin "1") (pinfunction "VIN_1") (pintype "input"))
      (node (ref "IDC1") (pin "3") (pinfunction "3_3") (pintype "bidirectional"))
      (node (ref "POWER-SELECT") (pin "1") (pinfunction "1_1") (pintype "passive"))
    )
    (net (code "48") (name "WIZ_INT") (class "Default")
      (node (ref "IC1") (pin "36") (pinfunction "INTN_36") (pintype "bidirectional"))
      (node (ref "R10") (pin "1") (pinfunction "1_1") (pintype "passive"))
    )
    (net (code "49") (name "unconnected-(IC1-DNC-Pad7)") (class "Default")
      (node (ref "IC1") (pin "7") (pinfunction "DNC_7") (pintype "bidirectional"))
    )
    (net (code "50") (name "unconnected-(IC1-NC_1-Pad12)") (class "Default")
      (node (ref "IC1") (pin "12") (pinfunction "NC_1_12") (pintype "bidirectional"))
    )
    (net (code "51") (name "unconnected-(IC1-NC_2-Pad13)") (class "Default")
      (node (ref "IC1") (pin "13") (pinfunction "NC_2_13") (pintype "bidirectional"))
    )
    (net (code "52") (name "unconnected-(IC1-NC_3-Pad46)") (class "Default")
      (node (ref "IC1") (pin "46") (pinfunction "NC_3_46") (pintype "bidirectional"))
    )
    (net (code "53") (name "unconnected-(IC1-NC_4-Pad47)") (class "Default")
      (node (ref "IC1") (pin "47") (pinfunction "NC_4_47") (pintype "bidirectional"))
    )
    (net (code "54") (name "unconnected-(IC1-VBG-Pad18)") (class "Default")
      (node (ref "IC1") (pin "18") (pinfunction "VBG_18") (pintype "bidirectional"))
    )
    (net (code "55") (name "unconnected-(IC7-PadADC)") (class "Default")
      (node (ref "IC7") (pin "ADC") (pinfunction "ADC_ADC") (pintype "bidirectional"))
    )
    (net (code "56") (name "unconnected-(IC7-PadCS0)") (class "Default")
      (node (ref "IC7") (pin "CS0") (pinfunction "CS0_CS0") (pintype "bidirectional"))
    )
    (net (code "57") (name "unconnected-(IC7-PadIO9)") (class "Default")
      (node (ref "IC7") (pin "IO9") (pinfunction "IO9_IO9") (pintype "bidirectional"))
    )
    (net (code "58") (name "unconnected-(IC7-PadIO10)") (class "Default")
      (node (ref "IC7") (pin "IO10") (pinfunction "IO10_IO10") (pintype "bidirectional"))
    )
    (net (code "59") (name "unconnected-(IC7-PadIO16)") (class "Default")
      (node (ref "IC7") (pin "IO16") (pinfunction "IO16_IO16") (pintype "bidirectional"))
    )
    (net (code "60") (name "unconnected-(IC7-PadMISO)") (class "Default")
      (node (ref "IC7") (pin "MISO") (pinfunction "MISO_MISO") (pintype "bidirectional"))
    )
    (net (code "61") (name "unconnected-(IC7-PadMOSI)") (class "Default")
      (node (ref "IC7") (pin "MOSI") (pinfunction "MOSI_MOSI") (pintype "bidirectional"))
    )
    (net (code "62") (name "unconnected-(IC7-PadSCLK)") (class "Default")
      (node (ref "IC7") (pin "SCLK") (pinfunction "SCLK_SCLK") (pintype "bidirectional"))
    )
    (net (code "63") (name "unconnected-(J2-PadMP1)") (class "Default")
      (node (ref "J2") (pin "MP1") (pinfunction "MP1_MP1") (pintype "bidirectional"))
    )
    (net (code "64") (name "unconnected-(J2-PadMP2)") (class "Default")
      (node (ref "J2") (pin "MP2") (pinfunction "MP2_MP2") (pintype "bidirectional"))
    )
    (net (code "65") (name "unconnected-(J3-PadMP1)") (class "Default")
      (node (ref "J3") (pin "MP1") (pinfunction "MP1_MP1") (pintype "bidirectional"))
    )
    (net (code "66") (name "unconnected-(J3-PadMP2)") (class "Default")
      (node (ref "J3") (pin "MP2") (pinfunction "MP2_MP2") (pintype "bidirectional"))
    )
    (net (code "67") (name "unconnected-(NEOPIXEL1-DOUT-Pad2)") (class "Default")
      (node (ref "NEOPIXEL1") (pin "2") (pinfunction "DOUT_2") (pintype "bidirectional"))
    )
    (net (code "68") (name "unconnected-(POE-MODULE-PadVB1)") (class "Default")
      (node (ref "POE-MODULE") (pin "VB1") (pinfunction "VB1_VB1") (pintype "no_connect"))
    )
    (net (code "69") (name "unconnected-(POE-MODULE-PadVB2)") (class "Default")
      (node (ref "POE-MODULE") (pin "VB2") (pinfunction "VB2_VB2") (pintype "no_connect"))
    )
    (net (code "70") (name "unconnected-(POWER-SELECT-Pad4)") (class "Default")
      (node (ref "POWER-SELECT") (pin "4") (pinfunction "4_4") (pintype "passive"))
    )
    (net (code "71") (name "unconnected-(RN4-Pad1)") (class "Default")
      (node (ref "RN4") (pin "1") (pinfunction "1_1") (pintype "passive"))
    )
  )
)
